# Sheet1.net
KiCad netlist of a schematic drawn in Altium Designer
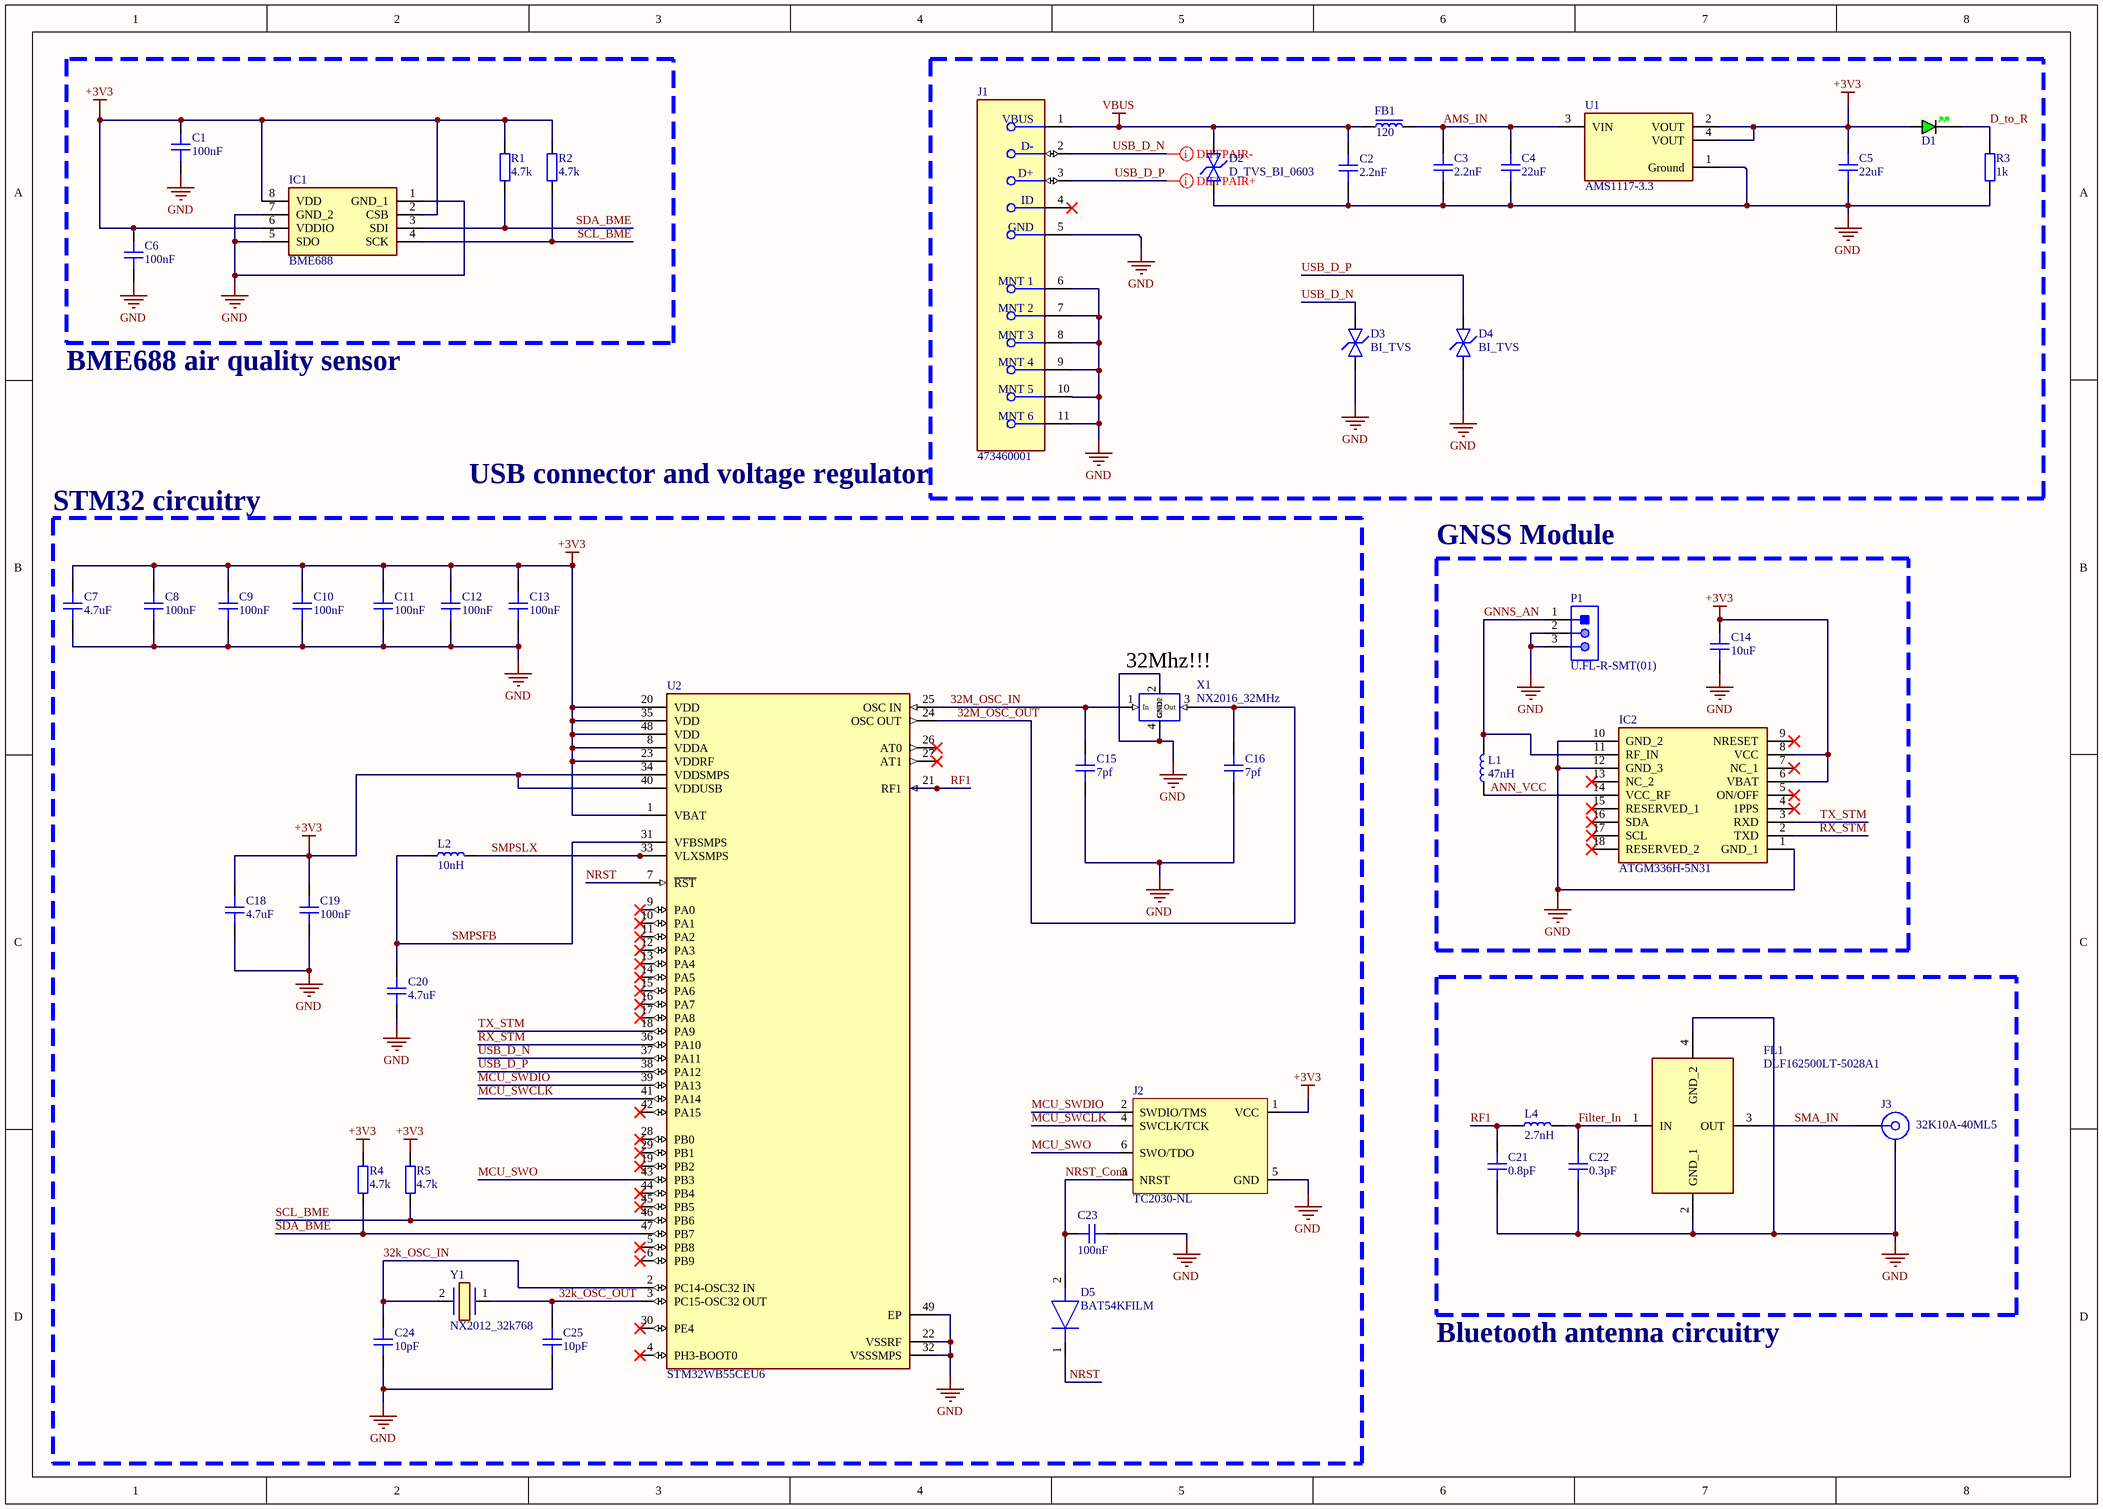
[diagram p0: Sheet1.SchDoc]

(export (version "E")
  (design (tool "Eeschema 10.0.6"))
  (components
    (comp (ref "C1")
      (value "100nF")
      (footprint "CAP_0402")
      (description "Capacitor SMD 0402")
      (libsource (lib "Schematic-Lib-PhilsLab") (part "CAP_0402"))
    )
    (comp (ref "C2")
      (value "2.2nF")
      (footprint "CAP_0603")
      (description "Capacitor SMD 0603")
      (libsource (lib "Schematic-Lib-PhilsLab") (part "CAP_0603"))
    )
    (comp (ref "C3")
      (value "2.2nF")
      (footprint "CAP_0603")
      (description "Capacitor SMD 0603")
      (libsource (lib "Schematic-Lib-PhilsLab") (part "CAP_0603"))
    )
    (comp (ref "C4")
      (value "22uF")
      (footprint "CAP_0805")
      (description "Capacitor SMD 0805")
      (libsource (lib "Schematic-Lib-PhilsLab") (part "CAP_0805"))
    )
    (comp (ref "C5")
      (value "22uF")
      (footprint "CAP_0805")
      (description "Capacitor SMD 0805")
      (libsource (lib "Schematic-Lib-PhilsLab") (part "CAP_0805"))
    )
    (comp (ref "C6")
      (value "100nF")
      (footprint "CAP_0402")
      (description "Capacitor SMD 0402")
      (libsource (lib "Schematic-Lib-PhilsLab") (part "CAP_0402"))
    )
    (comp (ref "C7")
      (value "4.7uF")
      (footprint "CAP_0603")
      (description "Capacitor SMD 0603")
      (libsource (lib "Schematic-Lib-PhilsLab") (part "CAP_0603"))
    )
    (comp (ref "C8")
      (value "100nF")
      (footprint "CAP_0402")
      (description "Capacitor SMD 0402")
      (libsource (lib "Schematic-Lib-PhilsLab") (part "CAP_0402"))
    )
    (comp (ref "C9")
      (value "100nF")
      (footprint "CAP_0402")
      (description "Capacitor SMD 0402")
      (libsource (lib "Schematic-Lib-PhilsLab") (part "CAP_0402"))
    )
    (comp (ref "C10")
      (value "100nF")
      (footprint "CAP_0402")
      (description "Capacitor SMD 0402")
      (libsource (lib "Schematic-Lib-PhilsLab") (part "CAP_0402"))
    )
    (comp (ref "C11")
      (value "100nF")
      (footprint "CAP_0402")
      (description "Capacitor SMD 0402")
      (libsource (lib "Schematic-Lib-PhilsLab") (part "CAP_0402"))
    )
    (comp (ref "C12")
      (value "100nF")
      (footprint "CAP_0402")
      (description "Capacitor SMD 0402")
      (libsource (lib "Schematic-Lib-PhilsLab") (part "CAP_0402"))
    )
    (comp (ref "C13")
      (value "100nF")
      (footprint "CAP_0402")
      (description "Capacitor SMD 0402")
      (libsource (lib "Schematic-Lib-PhilsLab") (part "CAP_0402"))
    )
    (comp (ref "C14")
      (value "10uF")
      (footprint "CAP_0603")
      (description "Capacitor SMD 0603")
      (libsource (lib "Schematic-Lib-PhilsLab") (part "CAP_0603"))
    )
    (comp (ref "C15")
      (value "7pf")
      (footprint "CAP_0402")
      (description "Capacitor SMD 0402")
      (libsource (lib "Schematic-Lib-PhilsLab") (part "CAP_0402"))
    )
    (comp (ref "C16")
      (value "7pf")
      (footprint "CAP_0402")
      (description "Capacitor SMD 0402")
      (libsource (lib "Schematic-Lib-PhilsLab") (part "CAP_0402"))
    )
    (comp (ref "C18")
      (value "4.7uF")
      (footprint "CAP_0603")
      (description "Capacitor SMD 0603")
      (libsource (lib "Schematic-Lib-PhilsLab") (part "CAP_0603"))
    )
    (comp (ref "C19")
      (value "100nF")
      (footprint "CAP_0402")
      (description "Capacitor SMD 0402")
      (libsource (lib "Schematic-Lib-PhilsLab") (part "CAP_0402"))
    )
    (comp (ref "C20")
      (value "4.7uF")
      (footprint "CAP_0603")
      (description "Capacitor SMD 0603")
      (libsource (lib "Schematic-Lib-PhilsLab") (part "CAP_0603"))
    )
    (comp (ref "C21")
      (value "0.8pF")
      (footprint "CAP_0402")
      (description "Capacitor SMD 0402")
      (libsource (lib "Schematic-Lib-PhilsLab") (part "CAP_0402"))
    )
    (comp (ref "C22")
      (value "0.3pF")
      (footprint "CAP_0402")
      (description "Capacitor SMD 0402")
      (libsource (lib "Schematic-Lib-PhilsLab") (part "CAP_0402"))
    )
    (comp (ref "C23")
      (value "100nF")
      (footprint "CAP_0402")
      (description "Capacitor SMD 0402")
      (libsource (lib "Schematic-Lib-PhilsLab") (part "CAP_0402"))
    )
    (comp (ref "C24")
      (value "10pF")
      (footprint "CAP_0402")
      (description "Capacitor SMD 0402")
      (libsource (lib "Schematic-Lib-PhilsLab") (part "CAP_0402"))
    )
    (comp (ref "C25")
      (value "10pF")
      (footprint "CAP_0402")
      (description "Capacitor SMD 0402")
      (libsource (lib "Schematic-Lib-PhilsLab") (part "CAP_0402"))
    )
    (comp (ref "D1")
      (value "GREEN")
      (footprint "LED_0402_GREEN")
      (description "LED 0402 GREEN SMD")
      (libsource (lib "Schematic-Lib-PhilsLab") (part "LED_0402_GREEN"))
    )
    (comp (ref "D2")
      (value "D_TVS_BI_0603")
      (footprint "D_0603")
      (description "Diode TVS / ESD Bidirectional 0603")
      (libsource (lib "Schematic-Lib-PhilsLab") (part "D_TVS_BI_0603"))
    )
    (comp (ref "D3")
      (value "BI_TVS")
      (footprint "D_0603")
      (description "Diode TVS / ESD Bidirectional 0603")
      (libsource (lib "Schematic-Lib-PhilsLab") (part "D_TVS_BI_0603"))
    )
    (comp (ref "D4")
      (value "BI_TVS")
      (footprint "D_0603")
      (description "Diode TVS / ESD Bidirectional 0603")
      (libsource (lib "Schematic-Lib-PhilsLab") (part "D_TVS_BI_0603"))
    )
    (comp (ref "D5")
      (value "BAT54KFILM")
      (footprint "SamacSys:SODFL1608X70N")
      (description "Diode")
      (fields (field (name "MOUSER PART NUMBER") "511-BAT54KFILM"))
      (libsource (lib "*") (part "BAT54KFILM"))
    )
    (comp (ref "FB1")
      (value "120")
      (footprint "FB_0603")
      (description "Ferrite Bead SMD 0603")
      (libsource (lib "Schematic-Lib-PhilsLab") (part "FB_0603"))
    )
    (comp (ref "FL1")
      (value "DLF162500LT-5028A1")
      (footprint "SamacSys:DLF162500LT5028A1")
      (description "Filter")
      (fields (field (name "MOUSER PART NUMBER") "810-DLF16250LT5028A1"))
      (libsource (lib "*") (part "DLF162500LT-5028A1"))
    )
    (comp (ref "IC1")
      (value "BME688")
      (footprint "SamacSys:BME688")
      (description "Integrated Circuit")
      (fields (field (name "MOUSER PART NUMBER") "262-BME688"))
      (libsource (lib "*") (part "BME688"))
    )
    (comp (ref "IC2")
      (value "ATGM336H-5N31")
      (footprint "SamacSys:ATGM336H5N31")
      (description "Integrated Circuit")
      (libsource (lib "*") (part "ATGM336H-5N31"))
    )
    (comp (ref "J1")
      (value "473460001")
      (footprint "FP-473460001-MFG")
      (description "CONN RCPT USB2.0 MICRO B SMD R/A")
      (fields
        (field (name "OCTOPART") "https://octopart.com/47346-0001-molex-7164928")
        (field (name "MANUFACTURER") "Molex")
      )
      (libsource (lib "Altium Content Vault") (part "53ae1f1d9b557310b43ca686e5bb76a"))
    )
    (comp (ref "J2")
      (value "TC2030-NL")
      (footprint "TC2030-NL-FP")
      (description "Tag-Connect No-Solder SWD Debug Connector (No Legs) DO NOT PLACE")
      (fields
        (field (name "MANUFACTURER") "Tag-Connect")
        (field (name "MANUFACTURER PART NUMBER") "TC2030-NL-FP")
      )
      (libsource (lib "Schematic-Lib-PhilsLab") (part "TC2030-NL"))
    )
    (comp (ref "J3")
      (value "32K10A-40ML5")
      (footprint "ROS-32K10A-40ML5_V")
      (description "SMA Straight Jack, Up to 12.4 GHz, -55 to 155 degC")
      (fields (field (name "MANUFACTURER") "Rosenberger"))
      (libsource (lib "Altium Content Vault") (part "ROS-CN-1F-RF1-A"))
    )
    (comp (ref "L1")
      (value "47nH")
      (footprint "IND_0402")
      (description "Inductor SMD 0402")
      (libsource (lib "Schematic-Lib-PhilsLab") (part "IND_0402"))
    )
    (comp (ref "L2")
      (value "10nH")
      (footprint "IND_0603")
      (description "Inductor SMD 0603")
      (libsource (lib "Schematic-Lib-PhilsLab") (part "IND_0603"))
    )
    (comp (ref "L4")
      (value "2.7nH")
      (footprint "IND_0402")
      (description "Inductor SMD 0402")
      (libsource (lib "Schematic-Lib-PhilsLab") (part "IND_0402"))
    )
    (comp (ref "P1")
      (value "U.FL-R-SMT(01)")
      (footprint "HRS-U.FL-R-SMT(10)_V")
      (description "CONN RECPT ULTRA-MINI COAX SMD")
      (fields (field (name "MANUFACTURER") "Hirose Electric") (field (name "APPROVAL CATEGORY") "UL94V-0"))
      (libsource (lib "Altium Content Vault") (part "CN-1P-M-R3"))
    )
    (comp (ref "R1")
      (value "4.7k")
      (footprint "RES_0603")
      (description "Resistor SMD 0603")
      (libsource (lib "Schematic-Lib-PhilsLab") (part "RES_0603"))
    )
    (comp (ref "R2")
      (value "4.7k")
      (footprint "RES_0603")
      (description "Resistor SMD 0603")
      (libsource (lib "Schematic-Lib-PhilsLab") (part "RES_0603"))
    )
    (comp (ref "R3")
      (value "1k")
      (footprint "RES_0402")
      (description "Resistor SMD 0402")
      (libsource (lib "Schematic-Lib-PhilsLab") (part "RES_0402"))
    )
    (comp (ref "R4")
      (value "4.7k")
      (footprint "RES_0402")
      (description "Resistor SMD 0402")
      (libsource (lib "Schematic-Lib-PhilsLab") (part "RES_0402"))
    )
    (comp (ref "R5")
      (value "4.7k")
      (footprint "RES_0402")
      (description "Resistor SMD 0402")
      (libsource (lib "Schematic-Lib-PhilsLab") (part "RES_0402"))
    )
    (comp (ref "U1")
      (value "AMS1117-3.3")
      (footprint "FP-AMS1117-IPC_C")
      (description "LDO Voltage Regulators 1A, 3.3V")
      (fields
        (field (name "OCTOPART") "https://octopart.com/ams1117-3.3-advanced+monolithic+systems-25899300")
        (field (name "MANUFACTURER") "Advanced Monolithic Systems")
      )
      (libsource (lib "Altium Content Vault") (part "8bdbb5f8e77002000e30dd2845d0354"))
    )
    (comp (ref "U2")
      (value "STM32WB55CEU6")
      (footprint "FP-UFQFPN48-A0B9-MFG")
      (description "ULTRA-LOW-POWER DUAL CORE ARM CO")
      (fields
        (field (name "MANUFACTURER") "STMicroelectronics")
        (field (name "OCTOPART") "https://octopart.com/stm32wb55ceu6-stmicroelectronics-96611730")
      )
      (libsource (lib "Altium Content Vault") (part "eb21ff5a47d2ca5be7d501793015931"))
    )
    (comp (ref "X1")
      (value "NX2016_32MHz")
      (footprint "PCBComponent_1")
      (description "32 Megahertz crystal oscillator")
      (libsource (lib "Schlib1") (part "NX2016_32MHZ"))
    )
    (comp (ref "Y1")
      (value "NX2012_32k768")
      (footprint "SamacSys:NX2012SA32768KSTDMUB1")
      (description "Crystal or Oscillator")
      (fields
        (field (name "MANUFACTURER_PART_NUMBER") "NX2012SA-32.768K-STD-MUB-1")
        (field (name "MOUSER PART NUMBER") "344-NX2012SA32768K1")
      )
      (libsource (lib "*") (part "NX2012SA-32.768K-STD-MUB-1"))
    )
  )
  (nets
    (net (code "1") (name "+3V3") (class "Default")
      (node (ref "C1") (pin "2") (pinfunction "2_2") (pintype "passive"))
      (node (ref "C10") (pin "2") (pinfunction "2_2") (pintype "passive"))
      (node (ref "C11") (pin "2") (pinfunction "2_2") (pintype "passive"))
      (node (ref "C12") (pin "2") (pinfunction "2_2") (pintype "passive"))
      (node (ref "C13") (pin "2") (pinfunction "2_2") (pintype "passive"))
      (node (ref "C14") (pin "2") (pinfunction "2_2") (pintype "passive"))
      (node (ref "C18") (pin "2") (pinfunction "2_2") (pintype "passive"))
      (node (ref "C19") (pin "2") (pinfunction "2_2") (pintype "passive"))
      (node (ref "C5") (pin "2") (pinfunction "2_2") (pintype "passive"))
      (node (ref "C6") (pin "2") (pinfunction "2_2") (pintype "passive"))
      (node (ref "C7") (pin "2") (pinfunction "2_2") (pintype "passive"))
      (node (ref "C8") (pin "2") (pinfunction "2_2") (pintype "passive"))
      (node (ref "C9") (pin "2") (pinfunction "2_2") (pintype "passive"))
      (node (ref "D1") (pin "A") (pinfunction "A_A") (pintype "passive"))
      (node (ref "IC1") (pin "2") (pinfunction "CSB_2") (pintype "passive"))
      (node (ref "IC1") (pin "6") (pinfunction "VDDIO_6") (pintype "passive"))
      (node (ref "IC1") (pin "8") (pinfunction "VDD_8") (pintype "passive"))
      (node (ref "IC2") (pin "6") (pinfunction "VBAT_6") (pintype "passive"))
      (node (ref "IC2") (pin "8") (pinfunction "VCC_8") (pintype "passive"))
      (node (ref "J2") (pin "1") (pinfunction "VCC_1") (pintype "passive"))
      (node (ref "R1") (pin "2") (pinfunction "2_2") (pintype "passive"))
      (node (ref "R2") (pin "2") (pinfunction "2_2") (pintype "passive"))
      (node (ref "R4") (pin "2") (pinfunction "2_2") (pintype "passive"))
      (node (ref "R5") (pin "2") (pinfunction "2_2") (pintype "passive"))
      (node (ref "U1") (pin "2") (pinfunction "VOUT_2") (pintype "passive"))
      (node (ref "U1") (pin "4") (pinfunction "VOUT_4") (pintype "passive"))
      (node (ref "U2") (pin "1") (pinfunction "VBAT_1") (pintype "power_in"))
      (node (ref "U2") (pin "20") (pinfunction "VDD_20") (pintype "power_in"))
      (node (ref "U2") (pin "23") (pinfunction "VDDRF_23") (pintype "power_in"))
      (node (ref "U2") (pin "34") (pinfunction "VDDSMPS_34") (pintype "power_in"))
      (node (ref "U2") (pin "35") (pinfunction "VDD_35") (pintype "power_in"))
      (node (ref "U2") (pin "40") (pinfunction "VDDUSB_40") (pintype "power_in"))
      (node (ref "U2") (pin "48") (pinfunction "VDD_48") (pintype "power_in"))
      (node (ref "U2") (pin "8") (pinfunction "VDDA_8") (pintype "power_in"))
    )
    (net (code "2") (name "/32M_OSC_IN") (class "Default")
      (node (ref "C15") (pin "2") (pinfunction "2_2") (pintype "passive"))
      (node (ref "U2") (pin "25") (pinfunction "OSC_IN_25") (pintype "input"))
      (node (ref "X1") (pin "1") (pinfunction "In_1") (pintype "input"))
    )
    (net (code "3") (name "/32M_OSC_OUT") (class "Default")
      (node (ref "C16") (pin "2") (pinfunction "2_2") (pintype "passive"))
      (node (ref "U2") (pin "24") (pinfunction "OSC_OUT_24") (pintype "output"))
      (node (ref "X1") (pin "3") (pinfunction "Out_3") (pintype "input"))
    )
    (net (code "4") (name "/32k_OSC_IN") (class "Default")
      (node (ref "C24") (pin "2") (pinfunction "2_2") (pintype "passive"))
      (node (ref "U2") (pin "2") (pinfunction "PC14-OSC32_IN_2") (pintype "bidirectional"))
      (node (ref "Y1") (pin "2") (pinfunction "CRYSTAL_2_2") (pintype "passive"))
    )
    (net (code "5") (name "/32k_OSC_OUT") (class "Default")
      (node (ref "C25") (pin "2") (pinfunction "2_2") (pintype "passive"))
      (node (ref "U2") (pin "3") (pinfunction "PC15-OSC32_OUT_3") (pintype "bidirectional"))
      (node (ref "Y1") (pin "1") (pinfunction "CRSYTAL_1_1") (pintype "passive"))
    )
    (net (code "6") (name "/AMS_IN") (class "Default")
      (node (ref "C3") (pin "2") (pinfunction "2_2") (pintype "passive"))
      (node (ref "C4") (pin "2") (pinfunction "2_2") (pintype "passive"))
      (node (ref "FB1") (pin "2") (pinfunction "2_2") (pintype "passive"))
      (node (ref "U1") (pin "3") (pinfunction "VIN_3") (pintype "power_in"))
    )
    (net (code "7") (name "/ANN_VCC") (class "Default")
      (node (ref "IC2") (pin "14") (pinfunction "VCC_RF_14") (pintype "passive"))
      (node (ref "L1") (pin "1") (pinfunction "1_1") (pintype "passive"))
    )
    (net (code "8") (name "/D_to_R") (class "Default")
      (node (ref "D1") (pin "K") (pinfunction "K_K") (pintype "passive"))
      (node (ref "R3") (pin "2") (pinfunction "2_2") (pintype "passive"))
    )
    (net (code "9") (name "/Filter_In") (class "Default")
      (node (ref "C22") (pin "2") (pinfunction "2_2") (pintype "passive"))
      (node (ref "FL1") (pin "1") (pinfunction "IN_1") (pintype "passive"))
      (node (ref "L4") (pin "2") (pinfunction "2_2") (pintype "passive"))
    )
    (net (code "10") (name "/GNNS_AN") (class "Default")
      (node (ref "IC2") (pin "11") (pinfunction "RF_IN_11") (pintype "passive"))
      (node (ref "L1") (pin "2") (pinfunction "2_2") (pintype "passive"))
      (node (ref "P1") (pin "1") (pinfunction "1_1") (pintype "passive"))
    )
    (net (code "11") (name "/MCU_SWCLK") (class "Default")
      (node (ref "J2") (pin "4") (pinfunction "SWCLK/TCK_4") (pintype "passive"))
      (node (ref "U2") (pin "41") (pinfunction "PA14_41") (pintype "bidirectional"))
    )
    (net (code "12") (name "/MCU_SWDIO") (class "Default")
      (node (ref "J2") (pin "2") (pinfunction "SWDIO/TMS_2") (pintype "passive"))
      (node (ref "U2") (pin "39") (pinfunction "PA13_39") (pintype "bidirectional"))
    )
    (net (code "13") (name "/MCU_SWO") (class "Default")
      (node (ref "J2") (pin "6") (pinfunction "SWO/TDO_6") (pintype "passive"))
      (node (ref "U2") (pin "43") (pinfunction "PB3_43") (pintype "bidirectional"))
    )
    (net (code "14") (name "/NRST") (class "Default")
      (node (ref "D5") (pin "1") (pinfunction "K_1") (pintype "passive"))
      (node (ref "U2") (pin "7") (pinfunction "~{RST}_7") (pintype "input"))
    )
    (net (code "15") (name "/NRST_Conn") (class "Default")
      (node (ref "C23") (pin "2") (pinfunction "2_2") (pintype "passive"))
      (node (ref "D5") (pin "2") (pinfunction "A_2") (pintype "passive"))
      (node (ref "J2") (pin "3") (pinfunction "NRST_3") (pintype "passive"))
    )
    (net (code "16") (name "/RF1") (class "Default")
      (node (ref "C21") (pin "2") (pinfunction "2_2") (pintype "passive"))
      (node (ref "L4") (pin "1") (pinfunction "1_1") (pintype "passive"))
      (node (ref "U2") (pin "21") (pinfunction "RF1_21") (pintype "input"))
    )
    (net (code "17") (name "/RX_STM") (class "Default")
      (node (ref "IC2") (pin "2") (pinfunction "TXD_2") (pintype "passive"))
      (node (ref "U2") (pin "36") (pinfunction "PA10_36") (pintype "bidirectional"))
    )
    (net (code "18") (name "/SCL_BME") (class "Default")
      (node (ref "IC1") (pin "4") (pinfunction "SCK_4") (pintype "passive"))
      (node (ref "R2") (pin "1") (pinfunction "1_1") (pintype "passive"))
      (node (ref "R5") (pin "1") (pinfunction "1_1") (pintype "passive"))
      (node (ref "U2") (pin "46") (pinfunction "PB6_46") (pintype "bidirectional"))
    )
    (net (code "19") (name "/SDA_BME") (class "Default")
      (node (ref "IC1") (pin "3") (pinfunction "SDI_3") (pintype "passive"))
      (node (ref "R1") (pin "1") (pinfunction "1_1") (pintype "passive"))
      (node (ref "R4") (pin "1") (pinfunction "1_1") (pintype "passive"))
      (node (ref "U2") (pin "47") (pinfunction "PB7_47") (pintype "bidirectional"))
    )
    (net (code "20") (name "/SMA_IN") (class "Default")
      (node (ref "FL1") (pin "3") (pinfunction "OUT_3") (pintype "passive"))
      (node (ref "J3") (pin "1") (pinfunction "1_1") (pintype "passive"))
    )
    (net (code "21") (name "/SMPSFB") (class "Default")
      (node (ref "C20") (pin "2") (pinfunction "2_2") (pintype "passive"))
      (node (ref "L2") (pin "1") (pinfunction "1_1") (pintype "passive"))
      (node (ref "U2") (pin "31") (pinfunction "VFBSMPS_31") (pintype "power_in"))
    )
    (net (code "22") (name "/SMPSLX") (class "Default")
      (node (ref "L2") (pin "2") (pinfunction "2_2") (pintype "passive"))
      (node (ref "U2") (pin "33") (pinfunction "VLXSMPS_33") (pintype "power_in"))
    )
    (net (code "23") (name "/TX_STM") (class "Default")
      (node (ref "IC2") (pin "3") (pinfunction "RXD_3") (pintype "passive"))
      (node (ref "U2") (pin "18") (pinfunction "PA9_18") (pintype "bidirectional"))
    )
    (net (code "24") (name "/USB_D_N") (class "Default")
      (node (ref "D3") (pin "A") (pinfunction "A_A") (pintype "passive"))
      (node (ref "J1") (pin "2") (pinfunction "D-_2") (pintype "bidirectional"))
      (node (ref "U2") (pin "37") (pinfunction "PA11_37") (pintype "bidirectional"))
    )
    (net (code "25") (name "/USB_D_P") (class "Default")
      (node (ref "D4") (pin "A") (pinfunction "A_A") (pintype "passive"))
      (node (ref "J1") (pin "3") (pinfunction "D+_3") (pintype "bidirectional"))
      (node (ref "U2") (pin "38") (pinfunction "PA12_38") (pintype "bidirectional"))
    )
    (net (code "26") (name "GND") (class "Default")
      (node (ref "C1") (pin "1") (pinfunction "1_1") (pintype "passive"))
      (node (ref "C10") (pin "1") (pinfunction "1_1") (pintype "passive"))
      (node (ref "C11") (pin "1") (pinfunction "1_1") (pintype "passive"))
      (node (ref "C12") (pin "1") (pinfunction "1_1") (pintype "passive"))
      (node (ref "C13") (pin "1") (pinfunction "1_1") (pintype "passive"))
      (node (ref "C14") (pin "1") (pinfunction "1_1") (pintype "passive"))
      (node (ref "C15") (pin "1") (pinfunction "1_1") (pintype "passive"))
      (node (ref "C16") (pin "1") (pinfunction "1_1") (pintype "passive"))
      (node (ref "C18") (pin "1") (pinfunction "1_1") (pintype "passive"))
      (node (ref "C19") (pin "1") (pinfunction "1_1") (pintype "passive"))
      (node (ref "C2") (pin "1") (pinfunction "1_1") (pintype "passive"))
      (node (ref "C20") (pin "1") (pinfunction "1_1") (pintype "passive"))
      (node (ref "C21") (pin "1") (pinfunction "1_1") (pintype "passive"))
      (node (ref "C22") (pin "1") (pinfunction "1_1") (pintype "passive"))
      (node (ref "C23") (pin "1") (pinfunction "1_1") (pintype "passive"))
      (node (ref "C24") (pin "1") (pinfunction "1_1") (pintype "passive"))
      (node (ref "C25") (pin "1") (pinfunction "1_1") (pintype "passive"))
      (node (ref "C3") (pin "1") (pinfunction "1_1") (pintype "passive"))
      (node (ref "C4") (pin "1") (pinfunction "1_1") (pintype "passive"))
      (node (ref "C5") (pin "1") (pinfunction "1_1") (pintype "passive"))
      (node (ref "C6") (pin "1") (pinfunction "1_1") (pintype "passive"))
      (node (ref "C7") (pin "1") (pinfunction "1_1") (pintype "passive"))
      (node (ref "C8") (pin "1") (pinfunction "1_1") (pintype "passive"))
      (node (ref "C9") (pin "1") (pinfunction "1_1") (pintype "passive"))
      (node (ref "D2") (pin "K") (pinfunction "K_K") (pintype "passive"))
      (node (ref "D3") (pin "K") (pinfunction "K_K") (pintype "passive"))
      (node (ref "D4") (pin "K") (pinfunction "K_K") (pintype "passive"))
      (node (ref "FL1") (pin "2") (pinfunction "GND_1_2") (pintype "passive"))
      (node (ref "FL1") (pin "4") (pinfunction "GND_2_4") (pintype "passive"))
      (node (ref "IC1") (pin "1") (pinfunction "GND_1_1") (pintype "passive"))
      (node (ref "IC1") (pin "5") (pinfunction "SDO_5") (pintype "passive"))
      (node (ref "IC1") (pin "7") (pinfunction "GND_2_7") (pintype "passive"))
      (node (ref "IC2") (pin "1") (pinfunction "GND_1_1") (pintype "passive"))
      (node (ref "IC2") (pin "10") (pinfunction "GND_2_10") (pintype "passive"))
      (node (ref "IC2") (pin "12") (pinfunction "GND_3_12") (pintype "passive"))
      (node (ref "J1") (pin "10") (pinfunction "MNT_5_10") (pintype "passive"))
      (node (ref "J1") (pin "11") (pinfunction "MNT_6_11") (pintype "passive"))
      (node (ref "J1") (pin "5") (pinfunction "GND_5") (pintype "power_in"))
      (node (ref "J1") (pin "6") (pinfunction "MNT_1_6") (pintype "passive"))
      (node (ref "J1") (pin "7") (pinfunction "MNT_2_7") (pintype "passive"))
      (node (ref "J1") (pin "8") (pinfunction "MNT_3_8") (pintype "passive"))
      (node (ref "J1") (pin "9") (pinfunction "MNT_4_9") (pintype "passive"))
      (node (ref "J2") (pin "5") (pinfunction "GND_5") (pintype "passive"))
      (node (ref "J3") (pin "MP") (pinfunction "MP_MP") (pintype "passive"))
      (node (ref "P1") (pin "2") (pinfunction "2_2") (pintype "passive"))
      (node (ref "P1") (pin "3") (pinfunction "3_3") (pintype "passive"))
      (node (ref "R3") (pin "1") (pinfunction "1_1") (pintype "passive"))
      (node (ref "U1") (pin "1") (pinfunction "Ground_1") (pintype "power_in"))
      (node (ref "U2") (pin "22") (pinfunction "VSSRF_22") (pintype "power_in"))
      (node (ref "U2") (pin "32") (pinfunction "VSSSMPS_32") (pintype "power_in"))
      (node (ref "U2") (pin "49") (pinfunction "EP_49") (pintype "power_in"))
      (node (ref "X1") (pin "2") (pinfunction "GND1_2") (pintype "open_collector"))
      (node (ref "X1") (pin "4") (pinfunction "GND2_4") (pintype "open_collector"))
    )
    (net (code "27") (name "VBUS") (class "Default")
      (node (ref "C2") (pin "2") (pinfunction "2_2") (pintype "passive"))
      (node (ref "D2") (pin "A") (pinfunction "A_A") (pintype "passive"))
      (node (ref "FB1") (pin "1") (pinfunction "1_1") (pintype "passive"))
      (node (ref "J1") (pin "1") (pinfunction "VBUS_1") (pintype "power_in"))
    )
    (net (code "28") (name "unconnected-(IC2-1PPS-Pad4)") (class "Default")
      (node (ref "IC2") (pin "4") (pinfunction "1PPS_4") (pintype "passive+no_connect"))
    )
    (net (code "29") (name "unconnected-(IC2-NC_1-Pad7)") (class "Default")
      (node (ref "IC2") (pin "7") (pinfunction "NC_1_7") (pintype "passive+no_connect"))
    )
    (net (code "30") (name "unconnected-(IC2-NC_2-Pad13)") (class "Default")
      (node (ref "IC2") (pin "13") (pinfunction "NC_2_13") (pintype "passive+no_connect"))
    )
    (net (code "31") (name "unconnected-(IC2-NRESET-Pad9)") (class "Default")
      (node (ref "IC2") (pin "9") (pinfunction "NRESET_9") (pintype "passive+no_connect"))
    )
    (net (code "32") (name "unconnected-(IC2-ON{slash}OFF-Pad5)") (class "Default")
      (node (ref "IC2") (pin "5") (pinfunction "ON/OFF_5") (pintype "passive+no_connect"))
    )
    (net (code "33") (name "unconnected-(IC2-RESERVED_1-Pad15)") (class "Default")
      (node (ref "IC2") (pin "15") (pinfunction "RESERVED_1_15") (pintype "passive+no_connect"))
    )
    (net (code "34") (name "unconnected-(IC2-RESERVED_2-Pad18)") (class "Default")
      (node (ref "IC2") (pin "18") (pinfunction "RESERVED_2_18") (pintype "passive+no_connect"))
    )
    (net (code "35") (name "unconnected-(IC2-SCL-Pad17)") (class "Default")
      (node (ref "IC2") (pin "17") (pinfunction "SCL_17") (pintype "passive+no_connect"))
    )
    (net (code "36") (name "unconnected-(IC2-SDA-Pad16)") (class "Default")
      (node (ref "IC2") (pin "16") (pinfunction "SDA_16") (pintype "passive+no_connect"))
    )
    (net (code "37") (name "unconnected-(J1-ID-Pad4)") (class "Default")
      (node (ref "J1") (pin "4") (pinfunction "ID_4") (pintype "passive+no_connect"))
    )
    (net (code "38") (name "unconnected-(U2-AT0-Pad26)") (class "Default")
      (node (ref "U2") (pin "26") (pinfunction "AT0_26") (pintype "output+no_connect"))
    )
    (net (code "39") (name "unconnected-(U2-AT1-Pad27)") (class "Default")
      (node (ref "U2") (pin "27") (pinfunction "AT1_27") (pintype "output+no_connect"))
    )
    (net (code "40") (name "unconnected-(U2-PA0-Pad9)") (class "Default")
      (node (ref "U2") (pin "9") (pinfunction "PA0_9") (pintype "bidirectional+no_connect"))
    )
    (net (code "41") (name "unconnected-(U2-PA1-Pad10)") (class "Default")
      (node (ref "U2") (pin "10") (pinfunction "PA1_10") (pintype "bidirectional+no_connect"))
    )
    (net (code "42") (name "unconnected-(U2-PA2-Pad11)") (class "Default")
      (node (ref "U2") (pin "11") (pinfunction "PA2_11") (pintype "bidirectional+no_connect"))
    )
    (net (code "43") (name "unconnected-(U2-PA3-Pad12)") (class "Default")
      (node (ref "U2") (pin "12") (pinfunction "PA3_12") (pintype "bidirectional+no_connect"))
    )
    (net (code "44") (name "unconnected-(U2-PA4-Pad13)") (class "Default")
      (node (ref "U2") (pin "13") (pinfunction "PA4_13") (pintype "bidirectional+no_connect"))
    )
    (net (code "45") (name "unconnected-(U2-PA5-Pad14)") (class "Default")
      (node (ref "U2") (pin "14") (pinfunction "PA5_14") (pintype "bidirectional+no_connect"))
    )
    (net (code "46") (name "unconnected-(U2-PA6-Pad15)") (class "Default")
      (node (ref "U2") (pin "15") (pinfunction "PA6_15") (pintype "bidirectional+no_connect"))
    )
    (net (code "47") (name "unconnected-(U2-PA7-Pad16)") (class "Default")
      (node (ref "U2") (pin "16") (pinfunction "PA7_16") (pintype "bidirectional+no_connect"))
    )
    (net (code "48") (name "unconnected-(U2-PA8-Pad17)") (class "Default")
      (node (ref "U2") (pin "17") (pinfunction "PA8_17") (pintype "bidirectional+no_connect"))
    )
    (net (code "49") (name "unconnected-(U2-PA15-Pad42)") (class "Default")
      (node (ref "U2") (pin "42") (pinfunction "PA15_42") (pintype "bidirectional+no_connect"))
    )
    (net (code "50") (name "unconnected-(U2-PB0-Pad28)") (class "Default")
      (node (ref "U2") (pin "28") (pinfunction "PB0_28") (pintype "bidirectional+no_connect"))
    )
    (net (code "51") (name "unconnected-(U2-PB1-Pad29)") (class "Default")
      (node (ref "U2") (pin "29") (pinfunction "PB1_29") (pintype "bidirectional+no_connect"))
    )
    (net (code "52") (name "unconnected-(U2-PB2-Pad19)") (class "Default")
      (node (ref "U2") (pin "19") (pinfunction "PB2_19") (pintype "bidirectional+no_connect"))
    )
    (net (code "53") (name "unconnected-(U2-PB4-Pad44)") (class "Default")
      (node (ref "U2") (pin "44") (pinfunction "PB4_44") (pintype "bidirectional+no_connect"))
    )
    (net (code "54") (name "unconnected-(U2-PB5-Pad45)") (class "Default")
      (node (ref "U2") (pin "45") (pinfunction "PB5_45") (pintype "bidirectional+no_connect"))
    )
    (net (code "55") (name "unconnected-(U2-PB8-Pad5)") (class "Default")
      (node (ref "U2") (pin "5") (pinfunction "PB8_5") (pintype "bidirectional+no_connect"))
    )
    (net (code "56") (name "unconnected-(U2-PB9-Pad6)") (class "Default")
      (node (ref "U2") (pin "6") (pinfunction "PB9_6") (pintype "bidirectional+no_connect"))
    )
    (net (code "57") (name "unconnected-(U2-PE4-Pad30)") (class "Default")
      (node (ref "U2") (pin "30") (pinfunction "PE4_30") (pintype "bidirectional+no_connect"))
    )
    (net (code "58") (name "unconnected-(U2-PH3-BOOT0-Pad4)") (class "Default")
      (node (ref "U2") (pin "4") (pinfunction "PH3-BOOT0_4") (pintype "bidirectional+no_connect"))
    )
  )
)
